# openSX70-dongle_v3-7.net
KiCad netlist of a schematic drawn in EAGLE
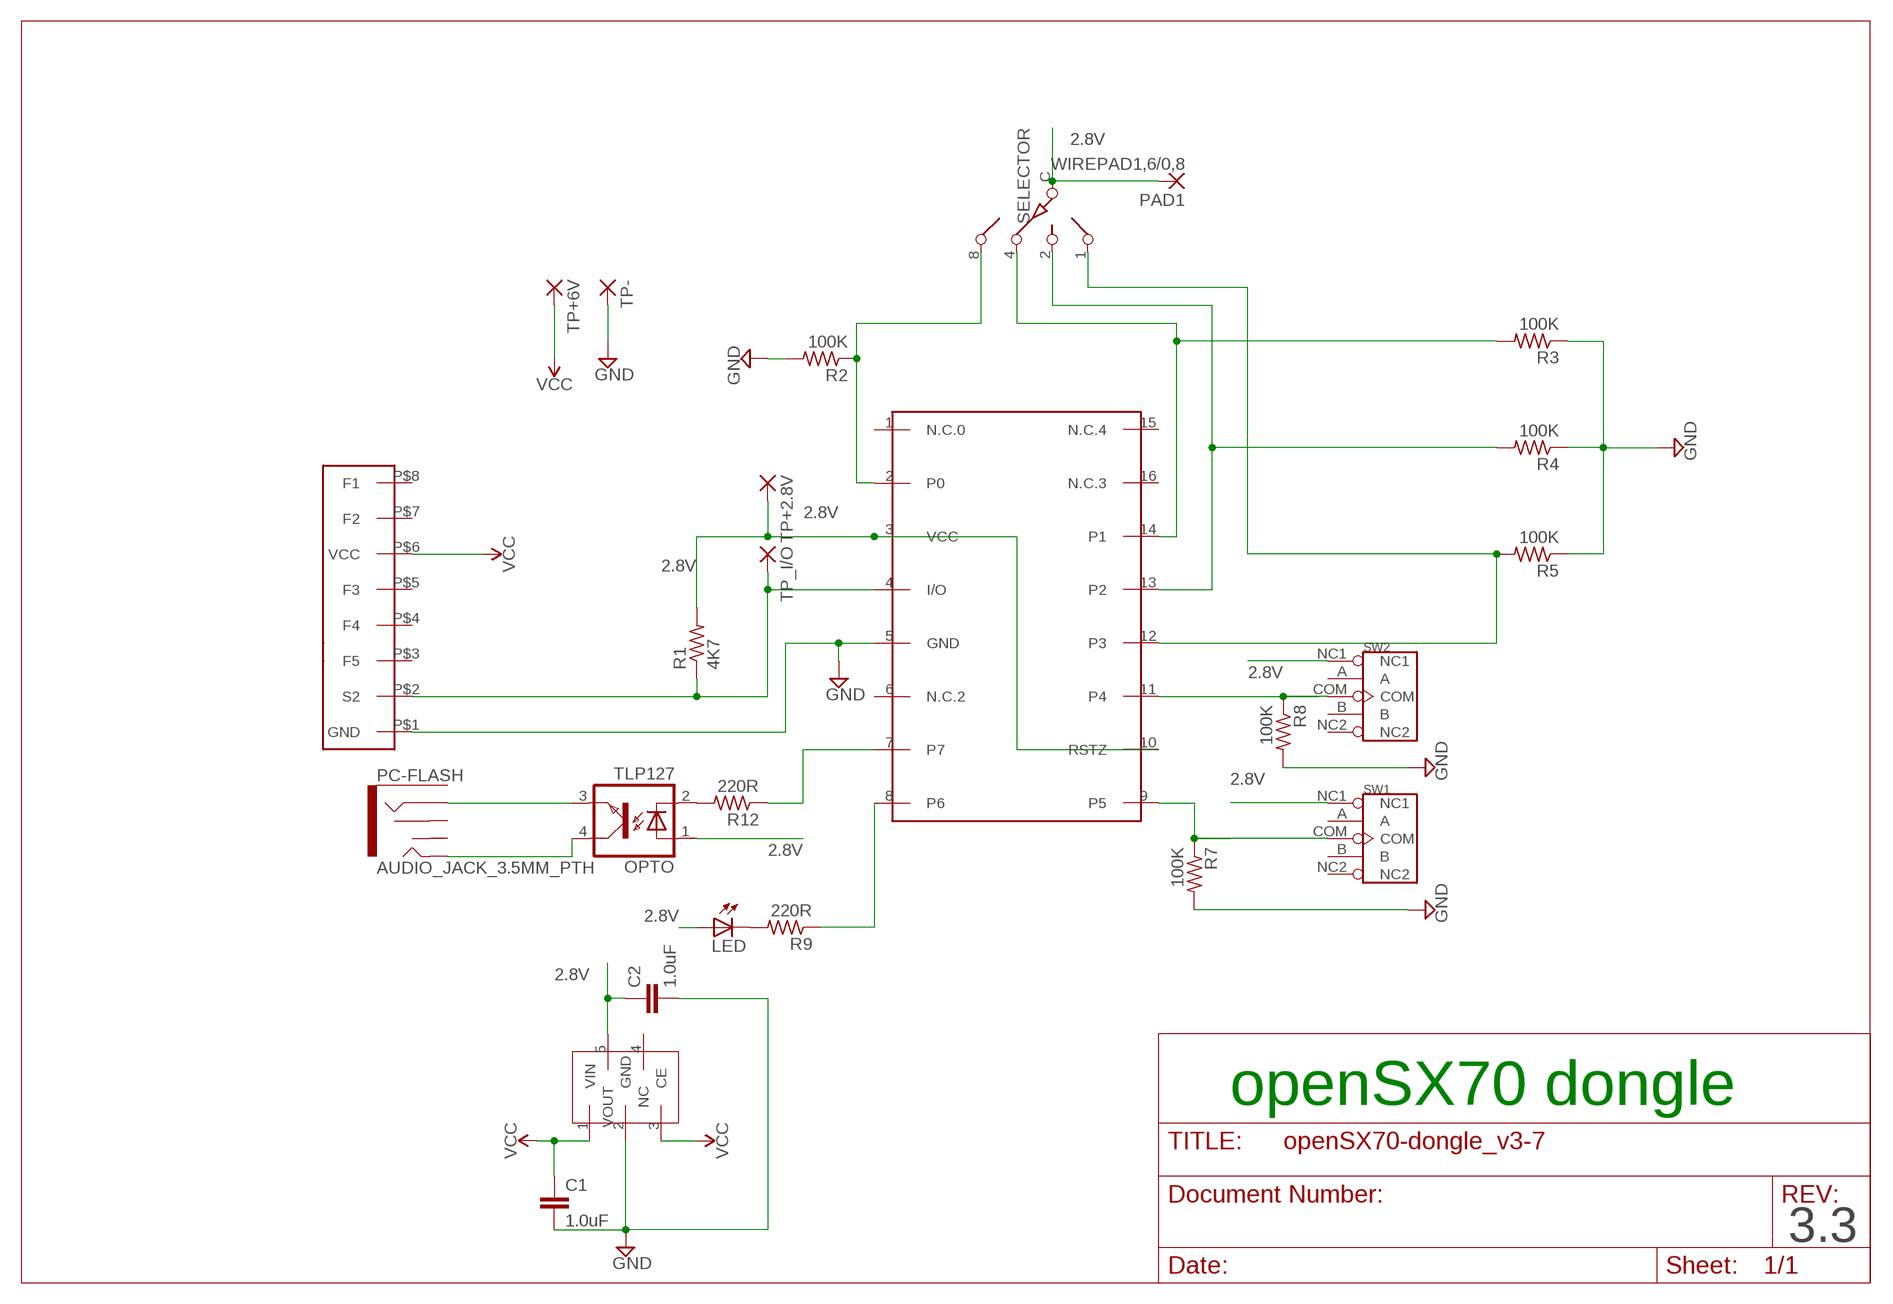
[diagram p0: schematic, sheet 1]

(export (version "E")
  (design (tool "Eeschema 10.0.6"))
  (components
    (comp (ref "C1")
      (value "1.0uF")
      (footprint "eagle-import:C0603")
      (libsource (lib "eagle-import") (part "C-EUC0603"))
    )
    (comp (ref "C2")
      (value "1.0uF")
      (footprint "eagle-import:C0603")
      (libsource (lib "eagle-import") (part "C-EUC0603"))
    )
    (comp (ref "DS2408")
      (value "DS2408")
      (footprint "eagle-import:SO16")
      (libsource (lib "eagle-import") (part "DS2408"))
    )
    (comp (ref "LED")
      (value "LED3MM")
      (footprint "eagle-import:LED3MM")
      (libsource (lib "eagle-import") (part "LED3MM"))
    )
    (comp (ref "OPTO")
      (value "TLP127")
      (footprint "eagle-import:SO-4")
      (libsource (lib "eagle-import") (part "TLP127"))
    )
    (comp (ref "PAD1")
      (value "WIREPAD1,6/0,8")
      (footprint "eagle-import:1,6_0,8")
      (libsource (lib "eagle-import") (part "WIREPAD1,6/0,8"))
    )
    (comp (ref "PC-FLASH")
      (value "AUDIO_JACK_3.5MM_PTH")
      (footprint "eagle-import:AUDIO-JACK")
      (libsource (lib "eagle-import") (part "AUDIO_JACK_3.5MM_PTH"))
    )
    (comp (ref "R1")
      (value "4K7")
      (footprint "eagle-import:M0805")
      (libsource (lib "eagle-import") (part "R-US_M0805"))
    )
    (comp (ref "R2")
      (value "100K")
      (footprint "eagle-import:M0805")
      (libsource (lib "eagle-import") (part "R-US_M0805"))
    )
    (comp (ref "R3")
      (value "100K")
      (footprint "eagle-import:M0805")
      (libsource (lib "eagle-import") (part "R-US_M0805"))
    )
    (comp (ref "R4")
      (value "100K")
      (footprint "eagle-import:M0805")
      (libsource (lib "eagle-import") (part "R-US_M0805"))
    )
    (comp (ref "R5")
      (value "100K")
      (footprint "eagle-import:M0805")
      (libsource (lib "eagle-import") (part "R-US_M0805"))
    )
    (comp (ref "R7")
      (value "100K")
      (footprint "eagle-import:M0805")
      (libsource (lib "eagle-import") (part "R-US_M0805"))
    )
    (comp (ref "R8")
      (value "100K")
      (footprint "eagle-import:M0805")
      (libsource (lib "eagle-import") (part "R-US_M0805"))
    )
    (comp (ref "R9")
      (value "220R")
      (footprint "eagle-import:M0805")
      (libsource (lib "eagle-import") (part "R-US_M0805"))
    )
    (comp (ref "R12")
      (value "220R")
      (footprint "eagle-import:M0805")
      (libsource (lib "eagle-import") (part "R-US_M0805"))
    )
    (comp (ref "REG")
      (value "NCP4688")
      (footprint "eagle-import:SOT-23-5")
      (libsource (lib "eagle-import") (part "NCP4688"))
    )
    (comp (ref "SELECTOR")
      (value "SW-C16")
      (footprint "eagle-import:SW-C16")
      (libsource (lib "eagle-import") (part "SW-C16"))
    )
    (comp (ref "SW1")
      (value "DIP-TOGGLE-SWITCH-ON-ON(3+2P-8.8X4.6MM)-90D")
      (footprint "eagle-import:SW5-2.0-8.8X4.4X4.7MM-90D")
      (fields (field (name "MPN") "3P-2.0-90D3P-2.0-90D-REINFORCE"))
      (libsource (lib "eagle-import") (part "DIP-TOGGLE-SWITCH-ON-ON(3+2P-8.8X4.6MM)-90D"))
    )
    (comp (ref "SW2")
      (value "DIP-TOGGLE-SWITCH-ON-ON(3+2P-8.8X4.6MM)-90D")
      (footprint "eagle-import:SW5-2.0-8.8X4.4X4.7MM-90D")
      (fields (field (name "MPN") "3P-2.0-90D3P-2.0-90D-REINFORCE"))
      (libsource (lib "eagle-import") (part "DIP-TOGGLE-SWITCH-ON-ON(3+2P-8.8X4.6MM)-90D"))
    )
    (comp (ref "TP+2.8V")
      (value "SMD2")
      (footprint "eagle-import:SMD1,27-2,54")
      (libsource (lib "eagle-import") (part "SMD2"))
    )
    (comp (ref "TP+6V")
      (value "SMD2")
      (footprint "eagle-import:SMD1,27-2,54")
      (libsource (lib "eagle-import") (part "SMD2"))
    )
    (comp (ref "TP-")
      (value "SMD2")
      (footprint "eagle-import:SMD1,27-2,54")
      (libsource (lib "eagle-import") (part "SMD2"))
    )
    (comp (ref "TP_I/O")
      (value "SMD2")
      (footprint "eagle-import:SMD1,27-2,54")
      (libsource (lib "eagle-import") (part "SMD2"))
    )
    (comp (ref "U$1")
      (value "FLASH-EDGE-CONNECTOR")
      (footprint "eagle-import:FLASH-EDGE-8")
      (libsource (lib "eagle-import") (part "FLASH-EDGE-CONNECTOR"))
    )
  )
  (nets
    (net (code "1") (name "/2.8V") (class "Default")
      (node (ref "C2") (pin "1") (pinfunction "1_1") (pintype "passive"))
      (node (ref "DS2408") (pin "10") (pinfunction "RSTZ_10") (pintype "bidirectional"))
      (node (ref "DS2408") (pin "3") (pinfunction "VCC_3") (pintype "bidirectional"))
      (node (ref "LED") (pin "A") (pinfunction "A_A") (pintype "passive"))
      (node (ref "OPTO") (pin "1") (pinfunction "A_1") (pintype "passive"))
      (node (ref "PAD1") (pin "1") (pinfunction "P_1") (pintype "passive"))
      (node (ref "R1") (pin "2") (pinfunction "2_2") (pintype "passive"))
      (node (ref "REG") (pin "5") (pinfunction "VOUT_5") (pintype "bidirectional"))
      (node (ref "SELECTOR") (pin "C") (pinfunction "C_C") (pintype "passive"))
      (node (ref "SW1") (pin "NC1") (pinfunction "NC1_NC1") (pintype "bidirectional"))
      (node (ref "SW2") (pin "NC1") (pinfunction "NC1_NC1") (pintype "bidirectional"))
      (node (ref "TP+2.8V") (pin "1") (pinfunction "P_1") (pintype "passive"))
    )
    (net (code "2") (name "GND") (class "Default")
      (node (ref "C1") (pin "2") (pinfunction "2_2") (pintype "passive"))
      (node (ref "C2") (pin "2") (pinfunction "2_2") (pintype "passive"))
      (node (ref "DS2408") (pin "5") (pinfunction "GND_5") (pintype "bidirectional"))
      (node (ref "R2") (pin "2") (pinfunction "2_2") (pintype "passive"))
      (node (ref "R3") (pin "1") (pinfunction "1_1") (pintype "passive"))
      (node (ref "R4") (pin "1") (pinfunction "1_1") (pintype "passive"))
      (node (ref "R5") (pin "1") (pinfunction "1_1") (pintype "passive"))
      (node (ref "R7") (pin "2") (pinfunction "2_2") (pintype "passive"))
      (node (ref "R8") (pin "2") (pinfunction "2_2") (pintype "passive"))
      (node (ref "REG") (pin "2") (pinfunction "GND_2") (pintype "bidirectional"))
      (node (ref "TP-") (pin "1") (pinfunction "P_1") (pintype "passive"))
      (node (ref "U$1") (pin "P$1") (pinfunction "GND_P$1") (pintype "bidirectional"))
    )
    (net (code "3") (name "Net-(DS2408-I{slash}O)") (class "Default")
      (node (ref "DS2408") (pin "4") (pinfunction "I/O_4") (pintype "bidirectional"))
      (node (ref "R1") (pin "1") (pinfunction "1_1") (pintype "passive"))
      (node (ref "TP_I/O") (pin "1") (pinfunction "P_1") (pintype "passive"))
      (node (ref "U$1") (pin "P$2") (pinfunction "S2_P$2") (pintype "bidirectional"))
    )
    (net (code "4") (name "Net-(DS2408-P0)") (class "Default")
      (node (ref "DS2408") (pin "2") (pinfunction "P0_2") (pintype "bidirectional"))
      (node (ref "R2") (pin "1") (pinfunction "1_1") (pintype "passive"))
      (node (ref "SELECTOR") (pin "8") (pinfunction "8_8") (pintype "passive"))
    )
    (net (code "5") (name "Net-(DS2408-P1)") (class "Default")
      (node (ref "DS2408") (pin "14") (pinfunction "P1_14") (pintype "bidirectional"))
      (node (ref "R3") (pin "2") (pinfunction "2_2") (pintype "passive"))
      (node (ref "SELECTOR") (pin "4") (pinfunction "4_4") (pintype "passive"))
    )
    (net (code "6") (name "Net-(DS2408-P2)") (class "Default")
      (node (ref "DS2408") (pin "13") (pinfunction "P2_13") (pintype "bidirectional"))
      (node (ref "R4") (pin "2") (pinfunction "2_2") (pintype "passive"))
      (node (ref "SELECTOR") (pin "2") (pinfunction "2_2") (pintype "passive"))
    )
    (net (code "7") (name "Net-(DS2408-P3)") (class "Default")
      (node (ref "DS2408") (pin "12") (pinfunction "P3_12") (pintype "bidirectional"))
      (node (ref "R5") (pin "2") (pinfunction "2_2") (pintype "passive"))
      (node (ref "SELECTOR") (pin "1") (pinfunction "1_1") (pintype "passive"))
    )
    (net (code "8") (name "Net-(DS2408-P4)") (class "Default")
      (node (ref "DS2408") (pin "11") (pinfunction "P4_11") (pintype "bidirectional"))
      (node (ref "R8") (pin "1") (pinfunction "1_1") (pintype "passive"))
      (node (ref "SW2") (pin "COM") (pinfunction "COM_COM") (pintype "bidirectional"))
    )
    (net (code "9") (name "Net-(DS2408-P5)") (class "Default")
      (node (ref "DS2408") (pin "9") (pinfunction "P5_9") (pintype "bidirectional"))
      (node (ref "R7") (pin "1") (pinfunction "1_1") (pintype "passive"))
      (node (ref "SW1") (pin "COM") (pinfunction "COM_COM") (pintype "bidirectional"))
    )
    (net (code "10") (name "Net-(DS2408-P6)") (class "Default")
      (node (ref "DS2408") (pin "8") (pinfunction "P6_8") (pintype "bidirectional"))
      (node (ref "R9") (pin "1") (pinfunction "1_1") (pintype "passive"))
    )
    (net (code "11") (name "Net-(DS2408-P7)") (class "Default")
      (node (ref "DS2408") (pin "7") (pinfunction "P7_7") (pintype "bidirectional"))
      (node (ref "R12") (pin "1") (pinfunction "1_1") (pintype "passive"))
    )
    (net (code "12") (name "Net-(LED-C)") (class "Default")
      (node (ref "LED") (pin "K") (pinfunction "C_K") (pintype "passive"))
      (node (ref "R9") (pin "2") (pinfunction "2_2") (pintype "passive"))
    )
    (net (code "13") (name "Net-(OPTO-C)") (class "Default")
      (node (ref "OPTO") (pin "2") (pinfunction "C_2") (pintype "passive"))
      (node (ref "R12") (pin "2") (pinfunction "2_2") (pintype "passive"))
    )
    (net (code "14") (name "Net-(OPTO-COL)") (class "Default")
      (node (ref "OPTO") (pin "4") (pinfunction "COL_4") (pintype "passive"))
      (node (ref "PC-FLASH") (pin "TIP") (pinfunction "TIP_TIP") (pintype "bidirectional"))
    )
    (net (code "15") (name "Net-(OPTO-EMIT)") (class "Default")
      (node (ref "OPTO") (pin "3") (pinfunction "EMIT_3") (pintype "passive"))
      (node (ref "PC-FLASH") (pin "RING") (pinfunction "RING_RING") (pintype "bidirectional"))
    )
    (net (code "16") (name "VCC") (class "Default")
      (node (ref "C1") (pin "1") (pinfunction "1_1") (pintype "passive"))
      (node (ref "REG") (pin "1") (pinfunction "VIN_1") (pintype "bidirectional"))
      (node (ref "REG") (pin "3") (pinfunction "CE_3") (pintype "bidirectional"))
      (node (ref "TP+6V") (pin "1") (pinfunction "P_1") (pintype "passive"))
      (node (ref "U$1") (pin "P$6") (pinfunction "VCC_P$6") (pintype "bidirectional"))
    )
    (net (code "17") (name "unconnected-(DS2408-N.C.0-Pad1)") (class "Default")
      (node (ref "DS2408") (pin "1") (pinfunction "N.C.0_1") (pintype "bidirectional"))
    )
    (net (code "18") (name "unconnected-(DS2408-N.C.2-Pad6)") (class "Default")
      (node (ref "DS2408") (pin "6") (pinfunction "N.C.2_6") (pintype "bidirectional"))
    )
    (net (code "19") (name "unconnected-(DS2408-N.C.3-Pad16)") (class "Default")
      (node (ref "DS2408") (pin "16") (pinfunction "N.C.3_16") (pintype "bidirectional"))
    )
    (net (code "20") (name "unconnected-(DS2408-N.C.4-Pad15)") (class "Default")
      (node (ref "DS2408") (pin "15") (pinfunction "N.C.4_15") (pintype "bidirectional"))
    )
    (net (code "21") (name "unconnected-(PC-FLASH-PadRSH)") (class "Default")
      (node (ref "PC-FLASH") (pin "RSH") (pinfunction "RSH_RSH") (pintype "bidirectional"))
    )
    (net (code "22") (name "unconnected-(PC-FLASH-PadSLEEVE)") (class "Default")
      (node (ref "PC-FLASH") (pin "SLEEVE") (pinfunction "SLEEVE_SLEEVE") (pintype "bidirectional"))
    )
    (net (code "23") (name "unconnected-(PC-FLASH-PadTSH)") (class "Default")
      (node (ref "PC-FLASH") (pin "TSH") (pinfunction "TSH_TSH") (pintype "bidirectional"))
    )
    (net (code "24") (name "unconnected-(REG-NC-Pad4)") (class "Default")
      (node (ref "REG") (pin "4") (pinfunction "NC_4") (pintype "bidirectional"))
    )
    (net (code "25") (name "unconnected-(SW1-PadA)") (class "Default")
      (node (ref "SW1") (pin "A") (pinfunction "A_A") (pintype "bidirectional"))
    )
    (net (code "26") (name "unconnected-(SW1-PadB)") (class "Default")
      (node (ref "SW1") (pin "B") (pinfunction "B_B") (pintype "bidirectional"))
    )
    (net (code "27") (name "unconnected-(SW1-PadNC2)") (class "Default")
      (node (ref "SW1") (pin "NC2") (pinfunction "NC2_NC2") (pintype "bidirectional"))
    )
    (net (code "28") (name "unconnected-(SW2-PadA)") (class "Default")
      (node (ref "SW2") (pin "A") (pinfunction "A_A") (pintype "bidirectional"))
    )
    (net (code "29") (name "unconnected-(SW2-PadB)") (class "Default")
      (node (ref "SW2") (pin "B") (pinfunction "B_B") (pintype "bidirectional"))
    )
    (net (code "30") (name "unconnected-(SW2-PadNC2)") (class "Default")
      (node (ref "SW2") (pin "NC2") (pinfunction "NC2_NC2") (pintype "bidirectional"))
    )
    (net (code "31") (name "unconnected-(U$1-F1-PadP$8)") (class "Default")
      (node (ref "U$1") (pin "P$8") (pinfunction "F1_P$8") (pintype "bidirectional"))
    )
    (net (code "32") (name "unconnected-(U$1-F2-PadP$7)") (class "Default")
      (node (ref "U$1") (pin "P$7") (pinfunction "F2_P$7") (pintype "bidirectional"))
    )
    (net (code "33") (name "unconnected-(U$1-F3-PadP$5)") (class "Default")
      (node (ref "U$1") (pin "P$5") (pinfunction "F3_P$5") (pintype "bidirectional"))
    )
    (net (code "34") (name "unconnected-(U$1-F4-PadP$4)") (class "Default")
      (node (ref "U$1") (pin "P$4") (pinfunction "F4_P$4") (pintype "bidirectional"))
    )
    (net (code "35") (name "unconnected-(U$1-F5-PadP$3)") (class "Default")
      (node (ref "U$1") (pin "P$3") (pinfunction "F5_P$3") (pintype "bidirectional"))
    )
  )
)
